# eagle_1.net
KiCad netlist of a schematic drawn in EAGLE
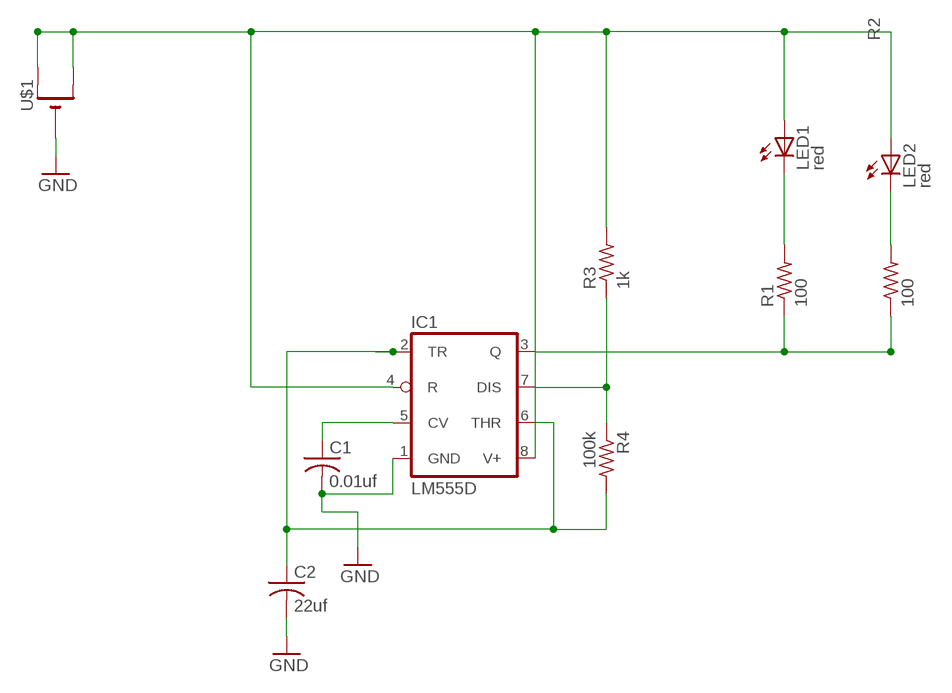
[diagram p0: schematic, sheet 1]

(export (version "E")
  (design (tool "Eeschema 10.0.6"))
  (components
    (comp (ref "C1")
      (value "0.01uf")
      (footprint "eagle-import:C0805")
      (libsource (lib "eagle-import") (part "C-USC0805"))
    )
    (comp (ref "C2")
      (value "22uf")
      (footprint "eagle-import:C0805")
      (libsource (lib "eagle-import") (part "C-USC0805"))
    )
    (comp (ref "IC1")
      (value "LM555D")
      (footprint "eagle-import:SO08")
      (libsource (lib "eagle-import") (part "555DLM"))
    )
    (comp (ref "LED1")
      (value "red")
      (footprint "eagle-import:CHIPLED_0805")
      (libsource (lib "eagle-import") (part "LEDCHIPLED_0805"))
    )
    (comp (ref "LED2")
      (value "red")
      (footprint "eagle-import:CHIPLED_0805")
      (libsource (lib "eagle-import") (part "LEDCHIPLED_0805"))
    )
    (comp (ref "R1")
      (value "100")
      (footprint "eagle-import:R0805")
      (libsource (lib "eagle-import") (part "R-US_R0805"))
    )
    (comp (ref "R2")
      (value "100")
      (footprint "eagle-import:R0805")
      (libsource (lib "eagle-import") (part "R-US_R0805"))
    )
    (comp (ref "R3")
      (value "1k")
      (footprint "eagle-import:R0805")
      (libsource (lib "eagle-import") (part "R-US_R0805"))
    )
    (comp (ref "R4")
      (value "100k")
      (footprint "eagle-import:R0805")
      (libsource (lib "eagle-import") (part "R-US_R0805"))
    )
    (comp (ref "U$1")
      (value "CR1220SMT")
      (footprint "eagle-import:CR1220-SMD")
      (libsource (lib "eagle-import") (part "CR1220SMT"))
    )
  )
  (nets
    (net (code "1") (name "GND") (class "Default")
      (node (ref "C1") (pin "2") (pinfunction "2_2") (pintype "passive"))
      (node (ref "C2") (pin "2") (pinfunction "2_2") (pintype "passive"))
      (node (ref "IC1") (pin "1") (pinfunction "GND_1") (pintype "power_in"))
      (node (ref "U$1") (pin "-") (pinfunction "-_-") (pintype "passive"))
    )
    (net (code "2") (name "Net-(IC1-CV)") (class "Default")
      (node (ref "C1") (pin "1") (pinfunction "1_1") (pintype "passive"))
      (node (ref "IC1") (pin "5") (pinfunction "CV_5") (pintype "input"))
    )
    (net (code "3") (name "Net-(IC1-DIS)") (class "Default")
      (node (ref "IC1") (pin "7") (pinfunction "DIS_7") (pintype "input"))
      (node (ref "R3") (pin "1") (pinfunction "1_1") (pintype "passive"))
      (node (ref "R4") (pin "1") (pinfunction "1_1") (pintype "passive"))
    )
    (net (code "4") (name "Net-(IC1-Q)") (class "Default")
      (node (ref "IC1") (pin "3") (pinfunction "Q_3") (pintype "output"))
      (node (ref "R1") (pin "1") (pinfunction "1_1") (pintype "passive"))
      (node (ref "R2") (pin "1") (pinfunction "1_1") (pintype "passive"))
    )
    (net (code "5") (name "Net-(IC1-R)") (class "Default")
      (node (ref "IC1") (pin "4") (pinfunction "R_4") (pintype "input"))
      (node (ref "IC1") (pin "8") (pinfunction "V+_8") (pintype "power_in"))
      (node (ref "LED1") (pin "A") (pinfunction "A_A") (pintype "passive"))
      (node (ref "LED2") (pin "A") (pinfunction "A_A") (pintype "passive"))
      (node (ref "R3") (pin "2") (pinfunction "2_2") (pintype "passive"))
      (node (ref "U$1") (pin "+$1") (pinfunction "+_+$1") (pintype "passive"))
      (node (ref "U$1") (pin "+$2") (pinfunction "+1_+$2") (pintype "passive"))
    )
    (net (code "6") (name "Net-(IC1-THR)") (class "Default")
      (node (ref "C2") (pin "1") (pinfunction "1_1") (pintype "passive"))
      (node (ref "IC1") (pin "2") (pinfunction "TR_2") (pintype "input"))
      (node (ref "IC1") (pin "6") (pinfunction "THR_6") (pintype "input"))
      (node (ref "R4") (pin "2") (pinfunction "2_2") (pintype "passive"))
    )
    (net (code "7") (name "Net-(LED1-PadC)") (class "Default")
      (node (ref "LED1") (pin "C") (pinfunction "C_C") (pintype "passive"))
      (node (ref "R1") (pin "2") (pinfunction "2_2") (pintype "passive"))
    )
    (net (code "8") (name "Net-(LED2-PadC)") (class "Default")
      (node (ref "LED2") (pin "C") (pinfunction "C_C") (pintype "passive"))
      (node (ref "R2") (pin "2") (pinfunction "2_2") (pintype "passive"))
    )
  )
)
